# preamp.net
KiCad netlist of a schematic drawn in Altium Designer
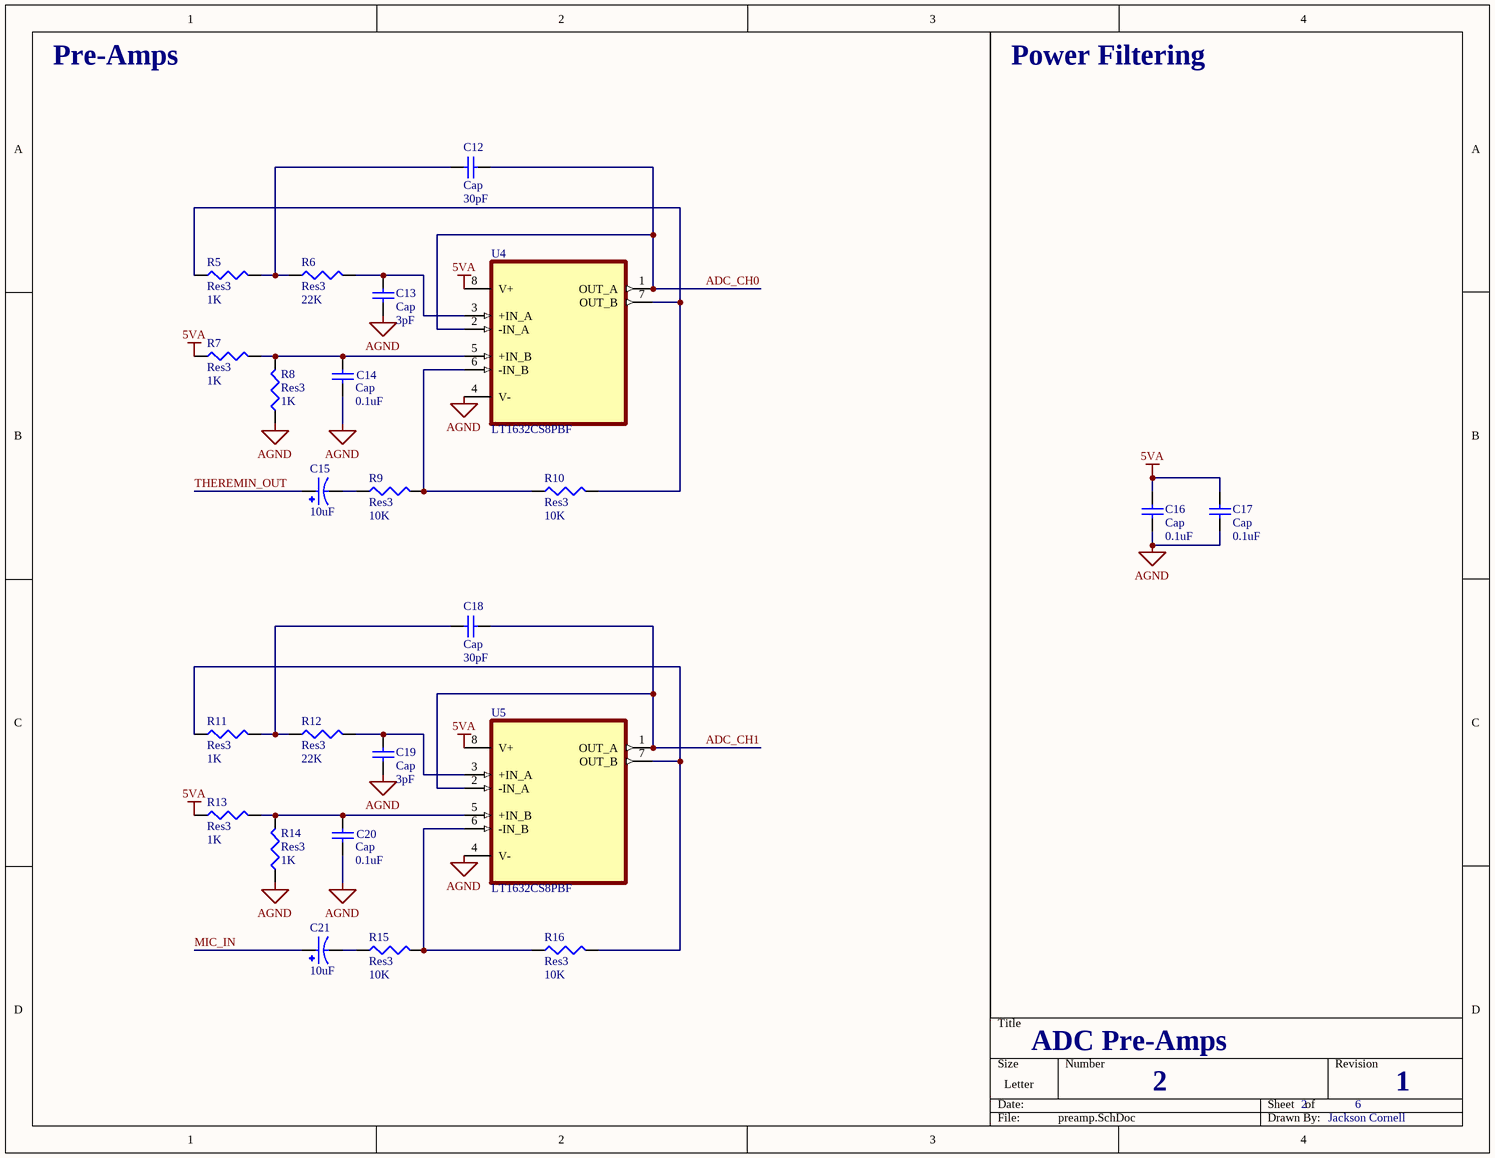
[diagram p0: preamp.SchDoc]

(export (version "E")
  (design (tool "Eeschema 10.0.6"))
  (components
    (comp (ref "C12")
      (value "Cap")
      (footprint "CAPC0805")
      (description "Capacitor")
      (fields (field (name "ALTIUM_VALUE") "30pF") (field (name "PUBLISHER") "Altium Limited"))
      (libsource (lib "Miscellaneous Devices") (part "Cap"))
    )
    (comp (ref "C13")
      (value "Cap")
      (footprint "CAPC0805")
      (description "Capacitor")
      (fields (field (name "ALTIUM_VALUE") "3pF") (field (name "PUBLISHER") "Altium Limited"))
      (libsource (lib "Miscellaneous Devices") (part "Cap"))
    )
    (comp (ref "C14")
      (value "Cap")
      (footprint "CAPC0805")
      (description "Capacitor")
      (fields (field (name "ALTIUM_VALUE") "0.1uF") (field (name "PUBLISHER") "Altium Limited"))
      (libsource (lib "Miscellaneous Devices") (part "Cap"))
    )
    (comp (ref "C15")
      (value "10uF")
      (footprint "CAPPRD500W50D500H1100")
      (description "Aluminum Electrolytic Capacitors, 220uF, 6.3V, -40 to 105C")
      (fields (field (name "MF") "Panasonic") (field (name "MP") "EEUFS0J221B"))
      (libsource (lib "EEUFS0J221B") (part "EEUFS0J221B"))
    )
    (comp (ref "C16")
      (value "Cap")
      (footprint "CAPC0805")
      (description "Capacitor")
      (fields (field (name "ALTIUM_VALUE") "0.1uF") (field (name "PUBLISHER") "Altium Limited"))
      (libsource (lib "Miscellaneous Devices") (part "Cap"))
    )
    (comp (ref "C17")
      (value "Cap")
      (footprint "CAPC0805")
      (description "Capacitor")
      (fields (field (name "ALTIUM_VALUE") "0.1uF") (field (name "PUBLISHER") "Altium Limited"))
      (libsource (lib "Miscellaneous Devices") (part "Cap"))
    )
    (comp (ref "C18")
      (value "Cap")
      (footprint "CAPC0805")
      (description "Capacitor")
      (fields (field (name "ALTIUM_VALUE") "30pF") (field (name "PUBLISHER") "Altium Limited"))
      (libsource (lib "Miscellaneous Devices") (part "Cap"))
    )
    (comp (ref "C19")
      (value "Cap")
      (footprint "CAPC0805")
      (description "Capacitor")
      (fields (field (name "ALTIUM_VALUE") "3pF") (field (name "PUBLISHER") "Altium Limited"))
      (libsource (lib "Miscellaneous Devices") (part "Cap"))
    )
    (comp (ref "C20")
      (value "Cap")
      (footprint "CAPC0805")
      (description "Capacitor")
      (fields (field (name "ALTIUM_VALUE") "0.1uF") (field (name "PUBLISHER") "Altium Limited"))
      (libsource (lib "Miscellaneous Devices") (part "Cap"))
    )
    (comp (ref "C21")
      (value "10uF")
      (footprint "CAPPRD500W50D500H1100")
      (description "Aluminum Electrolytic Capacitors, 220uF, 6.3V, -40 to 105C")
      (fields (field (name "MF") "Panasonic") (field (name "MP") "EEUFS0J221B"))
      (libsource (lib "EEUFS0J221B") (part "EEUFS0J221B"))
    )
    (comp (ref "R5")
      (value "Res3")
      (footprint "RES0805")
      (description "Resistor")
      (fields (field (name "ALTIUM_VALUE") "1K") (field (name "PUBLISHER") "Altium Limited"))
      (libsource (lib "Miscellaneous Devices") (part "Res3"))
    )
    (comp (ref "R6")
      (value "Res3")
      (footprint "RES0805")
      (description "Resistor")
      (fields (field (name "ALTIUM_VALUE") "22K") (field (name "PUBLISHER") "Altium Limited"))
      (libsource (lib "Miscellaneous Devices") (part "Res3"))
    )
    (comp (ref "R7")
      (value "Res3")
      (footprint "RES0805")
      (description "Resistor")
      (fields (field (name "ALTIUM_VALUE") "1K") (field (name "PUBLISHER") "Altium Limited"))
      (libsource (lib "Miscellaneous Devices") (part "Res3"))
    )
    (comp (ref "R8")
      (value "Res3")
      (footprint "RES0805")
      (description "Resistor")
      (fields (field (name "ALTIUM_VALUE") "1K") (field (name "PUBLISHER") "Altium Limited"))
      (libsource (lib "Miscellaneous Devices") (part "Res3"))
    )
    (comp (ref "R9")
      (value "Res3")
      (footprint "RES0805")
      (description "Resistor")
      (fields (field (name "ALTIUM_VALUE") "10K") (field (name "PUBLISHER") "Altium Limited"))
      (libsource (lib "Miscellaneous Devices") (part "Res3"))
    )
    (comp (ref "R10")
      (value "Res3")
      (footprint "RES0805")
      (description "Resistor")
      (fields (field (name "ALTIUM_VALUE") "10K") (field (name "PUBLISHER") "Altium Limited"))
      (libsource (lib "Miscellaneous Devices") (part "Res3"))
    )
    (comp (ref "R11")
      (value "Res3")
      (footprint "RES0805")
      (description "Resistor")
      (fields (field (name "ALTIUM_VALUE") "1K") (field (name "PUBLISHER") "Altium Limited"))
      (libsource (lib "Miscellaneous Devices") (part "Res3"))
    )
    (comp (ref "R12")
      (value "Res3")
      (footprint "RES0805")
      (description "Resistor")
      (fields (field (name "ALTIUM_VALUE") "22K") (field (name "PUBLISHER") "Altium Limited"))
      (libsource (lib "Miscellaneous Devices") (part "Res3"))
    )
    (comp (ref "R13")
      (value "Res3")
      (footprint "RES0805")
      (description "Resistor")
      (fields (field (name "ALTIUM_VALUE") "1K") (field (name "PUBLISHER") "Altium Limited"))
      (libsource (lib "Miscellaneous Devices") (part "Res3"))
    )
    (comp (ref "R14")
      (value "Res3")
      (footprint "RES0805")
      (description "Resistor")
      (fields (field (name "ALTIUM_VALUE") "1K") (field (name "PUBLISHER") "Altium Limited"))
      (libsource (lib "Miscellaneous Devices") (part "Res3"))
    )
    (comp (ref "R15")
      (value "Res3")
      (footprint "RES0805")
      (description "Resistor")
      (fields (field (name "ALTIUM_VALUE") "10K") (field (name "PUBLISHER") "Altium Limited"))
      (libsource (lib "Miscellaneous Devices") (part "Res3"))
    )
    (comp (ref "R16")
      (value "Res3")
      (footprint "RES0805")
      (description "Resistor")
      (fields (field (name "ALTIUM_VALUE") "10K") (field (name "PUBLISHER") "Altium Limited"))
      (libsource (lib "Miscellaneous Devices") (part "Res3"))
    )
    (comp (ref "U4")
      (value "LT1632CS8PBF")
      (footprint "SO-8_S")
      (description "45MHz, 45V/ms, Dual/Quad Rail-to-Rail Input and Output  Precision Op Amps")
      (libsource (lib "LT1632CS8PBF") (part "LT1632CS8PBF"))
    )
    (comp (ref "U5")
      (value "LT1632CS8PBF")
      (footprint "SO-8_S")
      (description "45MHz, 45V/ms, Dual/Quad Rail-to-Rail Input and Output  Precision Op Amps")
      (libsource (lib "LT1632CS8PBF") (part "LT1632CS8PBF"))
    )
  )
  (nets
    (net (code "1") (name "/ADC_CH0") (class "Default")
      (node (ref "C12") (pin "2") (pinfunction "2_2") (pintype "passive"))
      (node (ref "U4") (pin "1") (pinfunction "OUT_A_1") (pintype "output"))
      (node (ref "U4") (pin "2") (pinfunction "-IN_A_2") (pintype "input"))
    )
    (net (code "2") (name "/ADC_CH1") (class "Default")
      (node (ref "C18") (pin "2") (pinfunction "2_2") (pintype "passive"))
      (node (ref "U5") (pin "1") (pinfunction "OUT_A_1") (pintype "output"))
      (node (ref "U5") (pin "2") (pinfunction "-IN_A_2") (pintype "input"))
    )
    (net (code "3") (name "/MIC_IN") (class "Default")
      (node (ref "C21") (pin "P") (pinfunction "P_P") (pintype "passive"))
    )
    (net (code "4") (name "/THEREMIN_OUT") (class "Default")
      (node (ref "C15") (pin "P") (pinfunction "P_P") (pintype "passive"))
    )
    (net (code "5") (name "5VA") (class "Default")
      (node (ref "C16") (pin "2") (pinfunction "2_2") (pintype "passive"))
      (node (ref "C17") (pin "2") (pinfunction "2_2") (pintype "passive"))
      (node (ref "R13") (pin "1") (pinfunction "1_1") (pintype "passive"))
      (node (ref "R7") (pin "1") (pinfunction "1_1") (pintype "passive"))
      (node (ref "U4") (pin "8") (pinfunction "V+_8") (pintype "power_in"))
      (node (ref "U5") (pin "8") (pinfunction "V+_8") (pintype "power_in"))
    )
    (net (code "6") (name "AGND") (class "Default")
      (node (ref "C13") (pin "1") (pinfunction "1_1") (pintype "passive"))
      (node (ref "C14") (pin "1") (pinfunction "1_1") (pintype "passive"))
      (node (ref "C16") (pin "1") (pinfunction "1_1") (pintype "passive"))
      (node (ref "C17") (pin "1") (pinfunction "1_1") (pintype "passive"))
      (node (ref "C19") (pin "1") (pinfunction "1_1") (pintype "passive"))
      (node (ref "C20") (pin "1") (pinfunction "1_1") (pintype "passive"))
      (node (ref "R14") (pin "1") (pinfunction "1_1") (pintype "passive"))
      (node (ref "R8") (pin "1") (pinfunction "1_1") (pintype "passive"))
      (node (ref "U4") (pin "4") (pinfunction "V-_4") (pintype "power_in"))
      (node (ref "U5") (pin "4") (pinfunction "V-_4") (pintype "power_in"))
    )
    (net (code "7") (name "Net-(C12-Pad1)") (class "Default")
      (node (ref "C12") (pin "1") (pinfunction "1_1") (pintype "passive"))
      (node (ref "R5") (pin "2") (pinfunction "2_2") (pintype "passive"))
      (node (ref "R6") (pin "1") (pinfunction "1_1") (pintype "passive"))
    )
    (net (code "8") (name "Net-(C15-PadN)") (class "Default")
      (node (ref "C15") (pin "N") (pinfunction "N_N") (pintype "passive"))
      (node (ref "R9") (pin "1") (pinfunction "1_1") (pintype "passive"))
    )
    (net (code "9") (name "Net-(C18-Pad1)") (class "Default")
      (node (ref "C18") (pin "1") (pinfunction "1_1") (pintype "passive"))
      (node (ref "R11") (pin "2") (pinfunction "2_2") (pintype "passive"))
      (node (ref "R12") (pin "1") (pinfunction "1_1") (pintype "passive"))
    )
    (net (code "10") (name "Net-(C21-PadN)") (class "Default")
      (node (ref "C21") (pin "N") (pinfunction "N_N") (pintype "passive"))
      (node (ref "R15") (pin "1") (pinfunction "1_1") (pintype "passive"))
    )
    (net (code "11") (name "Net-(U4-+IN_A)") (class "Default")
      (node (ref "C13") (pin "2") (pinfunction "2_2") (pintype "passive"))
      (node (ref "R6") (pin "2") (pinfunction "2_2") (pintype "passive"))
      (node (ref "U4") (pin "3") (pinfunction "+IN_A_3") (pintype "input"))
    )
    (net (code "12") (name "Net-(U4-+IN_B)") (class "Default")
      (node (ref "C14") (pin "2") (pinfunction "2_2") (pintype "passive"))
      (node (ref "R7") (pin "2") (pinfunction "2_2") (pintype "passive"))
      (node (ref "R8") (pin "2") (pinfunction "2_2") (pintype "passive"))
      (node (ref "U4") (pin "5") (pinfunction "+IN_B_5") (pintype "input"))
    )
    (net (code "13") (name "Net-(U4--IN_B)") (class "Default")
      (node (ref "R10") (pin "1") (pinfunction "1_1") (pintype "passive"))
      (node (ref "R9") (pin "2") (pinfunction "2_2") (pintype "passive"))
      (node (ref "U4") (pin "6") (pinfunction "-IN_B_6") (pintype "input"))
    )
    (net (code "14") (name "Net-(U4-OUT_B)") (class "Default")
      (node (ref "R10") (pin "2") (pinfunction "2_2") (pintype "passive"))
      (node (ref "R5") (pin "1") (pinfunction "1_1") (pintype "passive"))
      (node (ref "U4") (pin "7") (pinfunction "OUT_B_7") (pintype "output"))
    )
    (net (code "15") (name "Net-(U5-+IN_A)") (class "Default")
      (node (ref "C19") (pin "2") (pinfunction "2_2") (pintype "passive"))
      (node (ref "R12") (pin "2") (pinfunction "2_2") (pintype "passive"))
      (node (ref "U5") (pin "3") (pinfunction "+IN_A_3") (pintype "input"))
    )
    (net (code "16") (name "Net-(U5-+IN_B)") (class "Default")
      (node (ref "C20") (pin "2") (pinfunction "2_2") (pintype "passive"))
      (node (ref "R13") (pin "2") (pinfunction "2_2") (pintype "passive"))
      (node (ref "R14") (pin "2") (pinfunction "2_2") (pintype "passive"))
      (node (ref "U5") (pin "5") (pinfunction "+IN_B_5") (pintype "input"))
    )
    (net (code "17") (name "Net-(U5--IN_B)") (class "Default")
      (node (ref "R15") (pin "2") (pinfunction "2_2") (pintype "passive"))
      (node (ref "R16") (pin "1") (pinfunction "1_1") (pintype "passive"))
      (node (ref "U5") (pin "6") (pinfunction "-IN_B_6") (pintype "input"))
    )
    (net (code "18") (name "Net-(U5-OUT_B)") (class "Default")
      (node (ref "R11") (pin "1") (pinfunction "1_1") (pintype "passive"))
      (node (ref "R16") (pin "2") (pinfunction "2_2") (pintype "passive"))
      (node (ref "U5") (pin "7") (pinfunction "OUT_B_7") (pintype "output"))
    )
  )
)
